# BMS029B_FETs.net
KiCad netlist of a schematic drawn in Altium Designer
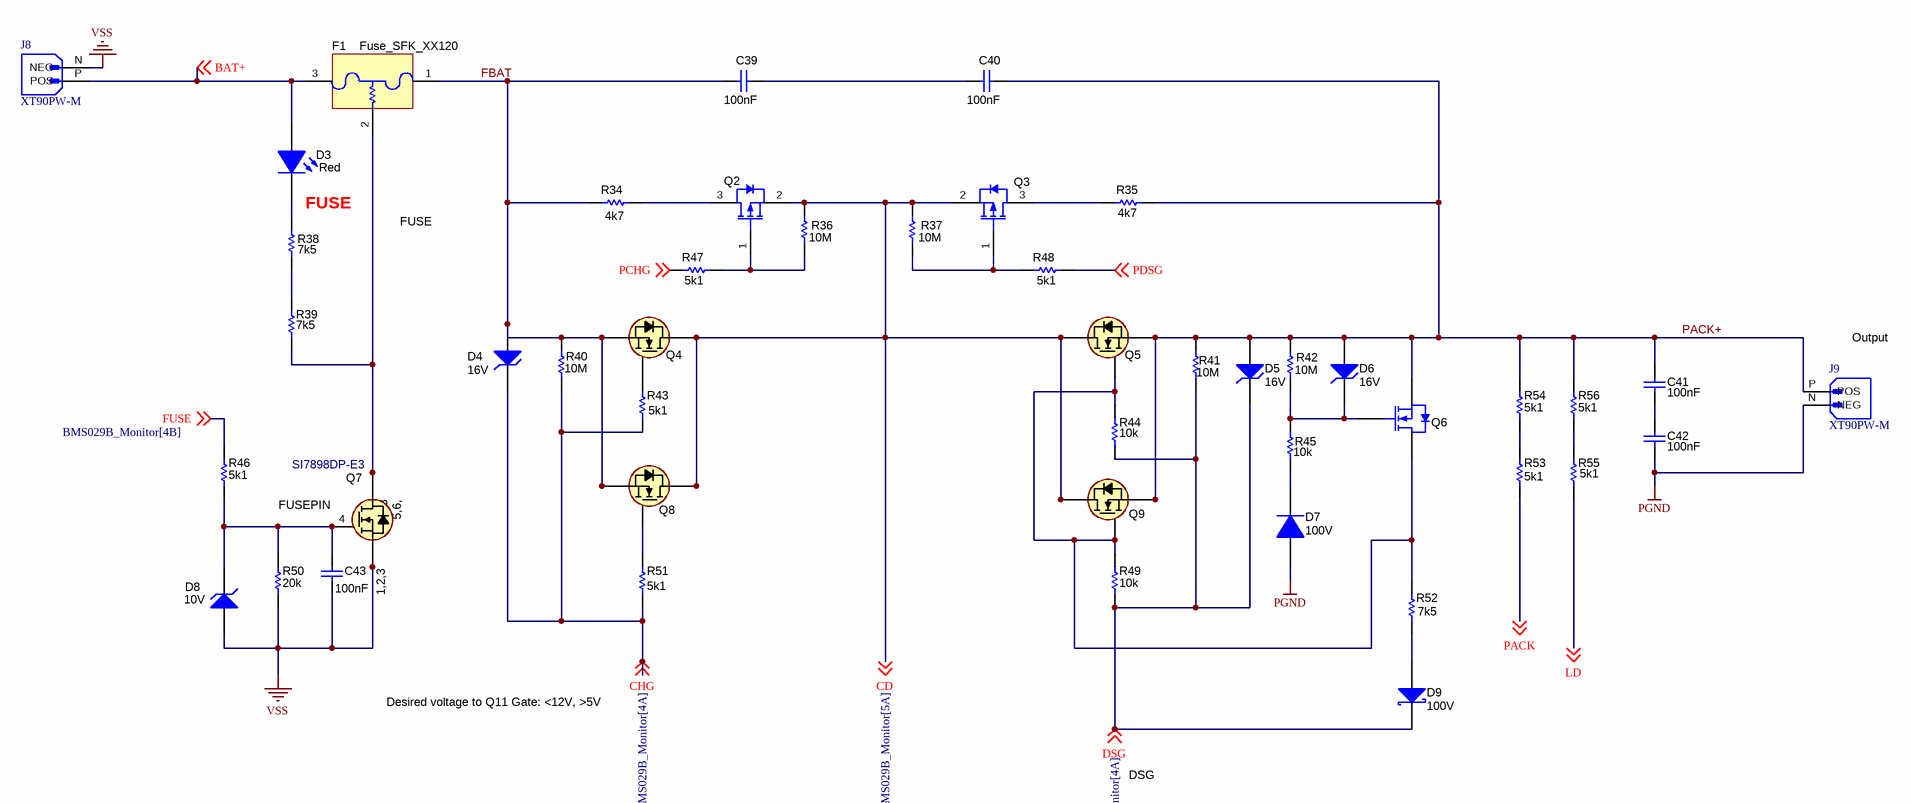
[diagram p0: BMS029B_FETs.SchDoc]

(export (version "E")
  (design (tool "Eeschema 10.0.6"))
  (components
    (comp (ref "C39")
      (value "100nF")
      (footprint "c0603")
      (description "CAP, CERM, 0.22 uF, 50 V, +/- 10%, X7R, 0603")
      (fields
        (field (name "MANUFACTURER") "TDK")
        (field (name "PARTNUMBER") "C1608X7R1H224K080AB")
        (field (name "PUBLISHER") "Texas Instruments")
      )
      (libsource (lib "worklib") (part "Capacitor"))
    )
    (comp (ref "C40")
      (value "100nF")
      (footprint "c0603")
      (description "CAP, CERM, 0.22 uF, 50 V, +/- 10%, X7R, 0603")
      (fields
        (field (name "MANUFACTURER") "TDK")
        (field (name "PARTNUMBER") "C1608X7R1H224K080AB")
        (field (name "PUBLISHER") "Texas Instruments")
      )
      (libsource (lib "worklib") (part "Capacitor"))
    )
    (comp (ref "C41")
      (value "100nF")
      (footprint "c0603")
      (description "CAP, CERM, 0.22 uF, 50 V, +/- 10%, X7R, 0603")
      (fields
        (field (name "MANUFACTURER") "TDK")
        (field (name "PARTNUMBER") "C1608X7R1H224K080AB")
        (field (name "PUBLISHER") "Texas Instruments")
      )
      (libsource (lib "worklib") (part "Capacitor"))
    )
    (comp (ref "C42")
      (value "100nF")
      (footprint "c0603")
      (description "CAP, CERM, 0.22 uF, 50 V, +/- 10%, X7R, 0603")
      (fields
        (field (name "MANUFACTURER") "TDK")
        (field (name "PARTNUMBER") "C1608X7R1H224K080AB")
        (field (name "PUBLISHER") "Texas Instruments")
      )
      (libsource (lib "worklib") (part "Capacitor"))
    )
    (comp (ref "C43")
      (value "100nF")
      (footprint "c0603")
      (description "CAP, CERM, 0.22 uF, 50 V, +/- 10%, X7R, 0603")
      (fields
        (field (name "PARTNUMBER") "C1608X7R1H224K080AB")
        (field (name "MANUFACTURER") "TDK")
        (field (name "PUBLISHER") "Texas Instruments")
      )
      (libsource (lib "worklib") (part "Capacitor"))
    )
    (comp (ref "D3")
      (value "Red")
      (footprint "WL-SMCW_RED")
      (description "LED, Red, SMD")
      (fields (field (name "MANUFACTURER") "Wurth Elektronik") (field (name "PARTNUMBER") "150060RS75000"))
      (libsource (lib "worklib") (part "CMP-0002947-3"))
    )
    (comp (ref "D4")
      (value "16V")
      (footprint "SOD-123")
      (description "Diode, Zener, 16 V, 500 mW, SOD-123")
      (fields (field (name "MANUFACTURER") "Diodes Inc.") (field (name "PARTNUMBER") "MMSZ5246B-7-F"))
      (libsource (lib "worklib") (part "Zener"))
    )
    (comp (ref "D5")
      (value "16V")
      (footprint "SOD-123")
      (description "Diode, Zener, 16 V, 500 mW, SOD-123")
      (fields (field (name "PARTNUMBER") "MMSZ5246B-7-F") (field (name "MANUFACTURER") "Diodes Inc."))
      (libsource (lib "worklib") (part "Zener"))
    )
    (comp (ref "D6")
      (value "16V")
      (footprint "SOD-123")
      (description "Diode, Zener, 16 V, 500 mW, SOD-123")
      (fields (field (name "PARTNUMBER") "MMSZ5246B-7-F") (field (name "MANUFACTURER") "Diodes Inc."))
      (libsource (lib "worklib") (part "Zener"))
    )
    (comp (ref "D7")
      (value "100V")
      (footprint "SOD-123")
      (description "Diode, Ultrafast, 100 V, 0.15 A, SOD-123")
      (fields (field (name "PARTNUMBER") "1N4148W-7-F") (field (name "MANUFACTURER") "Diodes Inc."))
      (libsource (lib "worklib") (part "CMP-0029001-2"))
    )
    (comp (ref "D8")
      (value "10V")
      (footprint "SOD-123")
      (description "Diode, Zener, 16 V, 500 mW, SOD-123")
      (fields (field (name "MANUFACTURER") "Diodes Inc.") (field (name "PARTNUMBER") "MMSZ5246B-7-F"))
      (libsource (lib "worklib") (part "Zener"))
    )
    (comp (ref "D9")
      (value "100V")
      (footprint "SOD-123")
      (description "Diode, Schottky, 100 V, 0.15 A, SOD-123")
      (fields (field (name "MANUFACTURER") "Diodes Inc.") (field (name "PARTNUMBER") "BAT46W-7-F"))
      (libsource (lib "worklib") (part "DIODE_SCHOTTKY"))
    )
    (comp (ref "F1")
      (value "Fuse_SFK_XX120")
      (footprint "120 Amperes SFM Series Self Control Protector(SCP)")
      (description "120 Amperes SFM Series Self Control Protector(SCP)")
      (fields (field (name "PARTNUMBER") "SFK-3030") (field (name "MANUFACTURER") "Dexerials Corporation"))
      (libsource (lib "worklib") (part "SFM-12120"))
    )
    (comp (ref "J8")
      (value "XT90PW-M")
      (footprint "AMASS_XT90PW-M")
      (description "Socket; DC supply; XT90; male; PIN: 2; on PCBs; THT; Colour: yellow")
      (fields (field (name "MF") "AMASS"))
      (libsource (lib "worklib") (part "XT90PW-M"))
    )
    (comp (ref "J9")
      (value "XT90PW-M")
      (footprint "AMASS_XT90PW-M")
      (description "Socket; DC supply; XT90; male; PIN: 2; on PCBs; THT; Colour: yellow")
      (fields (field (name "MF") "AMASS"))
      (libsource (lib "") (part "XT90PW-M_1"))
    )
    (comp (ref "Q2")
      (value "MOSFET_P_D3G1S2")
      (footprint "SOT-23")
      (description "MOSFET, P-CH, -150 V, -0.53 A, SOT-23")
      (libsource (lib "worklib") (part "MOSFET_P_D3G1S2"))
    )
    (comp (ref "Q3")
      (value "MOSFET_P_D3G1S2")
      (footprint "SOT-23")
      (description "MOSFET, P-CH, -150 V, -0.53 A, SOT-23")
      (libsource (lib "worklib") (part "MOSFET_P_D3G1S2"))
    )
    (comp (ref "Q4")
      (value "BSC160N15NS5ATMA1")
      (footprint "PG-TDSON-8")
      (description "MOSFET, N-CH, 150 V, 56 A, PG-TDSON-8")
      (fields
        (field (name "MANUFACTURER") "Infineon Technologies")
        (field (name "PUBLISHER") "Texas Instruments")
      )
      (libsource (lib "worklib") (part "MOSFET_N_D56789G"))
    )
    (comp (ref "Q5")
      (value "BSC160N15NS5ATMA1")
      (footprint "PG-TDSON-8")
      (description "MOSFET, N-CH, 150 V, 56 A, PG-TDSON-8")
      (fields
        (field (name "MANUFACTURER") "Infineon Technologies")
        (field (name "PUBLISHER") "Texas Instruments")
      )
      (libsource (lib "worklib") (part "MOSFET_N_D56789G"))
    )
    (comp (ref "Q6")
      (value "2N7002KW")
      (footprint "SOT-323")
      (description "MOSFET, N-CH, 60 V, 0.31 A, SOT-323")
      (fields
        (field (name "MANUFACTURER") "Fairchild Semiconductor")
        (field (name "PUBLISHER") "Texas Instruments")
      )
      (libsource (lib "worklib") (part "CMP-0000774-1"))
    )
    (comp (ref "Q7")
      (value "SI7898DP-E3")
      (footprint "PowerPAK_SO-8")
      (description "MOSFET, N-CH, 150 V, 13 A, PowerPACK SO-8")
      (fields
        (field (name "MANUFACTURER") "Infineon Technologies")
        (field (name "PARTNUMBER") "BSZ900N15NS3 G")
        (field (name "PUBLISHER") "Texas Instruments")
      )
      (libsource (lib "worklib") (part "SI7898DP-E3"))
    )
    (comp (ref "Q8")
      (value "BSC160N15NS5ATMA1")
      (footprint "PG-TDSON-8")
      (description "MOSFET, N-CH, 150 V, 56 A, PG-TDSON-8")
      (fields
        (field (name "MANUFACTURER") "Infineon Technologies")
        (field (name "PUBLISHER") "Texas Instruments")
      )
      (libsource (lib "worklib") (part "MOSFET_N_D56789G"))
    )
    (comp (ref "Q9")
      (value "BSC160N15NS5ATMA1")
      (footprint "PG-TDSON-8")
      (description "MOSFET, N-CH, 150 V, 56 A, PG-TDSON-8")
      (fields
        (field (name "MANUFACTURER") "Infineon Technologies")
        (field (name "PUBLISHER") "Texas Instruments")
      )
      (libsource (lib "worklib") (part "MOSFET_N_D56789G"))
    )
    (comp (ref "R34")
      (value "4k7")
      (footprint "2512")
      (description "RES, 20.0, 1%, 0.25 W, AEC-Q200 Grade 0, 1206")
      (fields (field (name "MANUFACTURER") "Vishay-Dale") (field (name "PARTNUMBER") "CRCW120620R0FKEA"))
      (libsource (lib "worklib") (part "Resistor_2512"))
    )
    (comp (ref "R35")
      (value "4k7")
      (footprint "2512")
      (description "RES, 20.0, 1%, 0.25 W, AEC-Q200 Grade 0, 1206")
      (fields (field (name "MANUFACTURER") "Vishay-Dale") (field (name "PARTNUMBER") "CRCW120620R0FKEA"))
      (libsource (lib "worklib") (part "Resistor_2512"))
    )
    (comp (ref "R36")
      (value "10M")
      (footprint "SMD 0805 res")
      (description "0.25 W, AEC-Q200 Grade 0, 0805")
      (fields (field (name "PARTNUMBER") "CRCW120620R0FKEA") (field (name "MANUFACTURER") "Vishay-Dale"))
      (libsource (lib "worklib") (part "Resistor_0805"))
    )
    (comp (ref "R37")
      (value "10M")
      (footprint "SMD 0805 res")
      (description "0.25 W, AEC-Q200 Grade 0, 0805")
      (fields (field (name "PARTNUMBER") "CRCW120620R0FKEA") (field (name "MANUFACTURER") "Vishay-Dale"))
      (libsource (lib "worklib") (part "Resistor_0805"))
    )
    (comp (ref "R38")
      (value "7k5")
      (footprint "SMD 0805 res")
      (description "0.25 W, AEC-Q200 Grade 0, 0805")
      (fields (field (name "MANUFACTURER") "Vishay-Dale") (field (name "PARTNUMBER") "CRCW120620R0FKEA"))
      (libsource (lib "worklib") (part "Resistor_0805"))
    )
    (comp (ref "R39")
      (value "7k5")
      (footprint "SMD 0805 res")
      (description "0.25 W, AEC-Q200 Grade 0, 0805")
      (fields (field (name "MANUFACTURER") "Vishay-Dale") (field (name "PARTNUMBER") "CRCW120620R0FKEA"))
      (libsource (lib "worklib") (part "Resistor_0805"))
    )
    (comp (ref "R40")
      (value "10M")
      (footprint "SMD 0805 res")
      (description "0.25 W, AEC-Q200 Grade 0, 0805")
      (fields (field (name "PARTNUMBER") "CRCW120620R0FKEA") (field (name "MANUFACTURER") "Vishay-Dale"))
      (libsource (lib "worklib") (part "Resistor_0805"))
    )
    (comp (ref "R41")
      (value "10M")
      (footprint "SMD 0805 res")
      (description "0.25 W, AEC-Q200 Grade 0, 0805")
      (fields (field (name "PARTNUMBER") "CRCW120620R0FKEA") (field (name "MANUFACTURER") "Vishay-Dale"))
      (libsource (lib "worklib") (part "Resistor_0805"))
    )
    (comp (ref "R42")
      (value "10M")
      (footprint "SMD 0805 res")
      (description "0.25 W, AEC-Q200 Grade 0, 0805")
      (fields (field (name "PARTNUMBER") "CRCW120620R0FKEA") (field (name "MANUFACTURER") "Vishay-Dale"))
      (libsource (lib "worklib") (part "Resistor_0805"))
    )
    (comp (ref "R43")
      (value "5k1")
      (footprint "SMD 0805 res")
      (description "0.25 W, AEC-Q200 Grade 0, 0805")
      (fields (field (name "PARTNUMBER") "CRCW120620R0FKEA") (field (name "MANUFACTURER") "Vishay-Dale"))
      (libsource (lib "worklib") (part "Resistor_0805"))
    )
    (comp (ref "R44")
      (value "10k")
      (footprint "SMD 0805 res")
      (description "0.25 W, AEC-Q200 Grade 0, 0805")
      (fields (field (name "PARTNUMBER") "CRCW120620R0FKEA") (field (name "MANUFACTURER") "Vishay-Dale"))
      (libsource (lib "worklib") (part "Resistor_0805"))
    )
    (comp (ref "R45")
      (value "10k")
      (footprint "SMD 0805 res")
      (description "0.25 W, AEC-Q200 Grade 0, 0805")
      (fields (field (name "PARTNUMBER") "CRCW120620R0FKEA") (field (name "MANUFACTURER") "Vishay-Dale"))
      (libsource (lib "worklib") (part "Resistor_0805"))
    )
    (comp (ref "R46")
      (value "5k1")
      (footprint "SMD 0805 res")
      (description "0.25 W, AEC-Q200 Grade 0, 0805")
      (fields (field (name "PARTNUMBER") "CRCW120620R0FKEA") (field (name "MANUFACTURER") "Vishay-Dale"))
      (libsource (lib "worklib") (part "Resistor_0805"))
    )
    (comp (ref "R47")
      (value "5k1")
      (footprint "SMD 0805 res")
      (description "0.25 W, AEC-Q200 Grade 0, 0805")
      (fields (field (name "PARTNUMBER") "CRCW120620R0FKEA") (field (name "MANUFACTURER") "Vishay-Dale"))
      (libsource (lib "worklib") (part "Resistor_0805"))
    )
    (comp (ref "R48")
      (value "5k1")
      (footprint "SMD 0805 res")
      (description "0.25 W, AEC-Q200 Grade 0, 0805")
      (fields (field (name "PARTNUMBER") "CRCW120620R0FKEA") (field (name "MANUFACTURER") "Vishay-Dale"))
      (libsource (lib "worklib") (part "Resistor_0805"))
    )
    (comp (ref "R49")
      (value "10k")
      (footprint "SMD 0805 res")
      (description "0.25 W, AEC-Q200 Grade 0, 0805")
      (fields (field (name "PARTNUMBER") "CRCW120620R0FKEA") (field (name "MANUFACTURER") "Vishay-Dale"))
      (libsource (lib "worklib") (part "Resistor_0805"))
    )
    (comp (ref "R50")
      (value "20k")
      (footprint "SMD 0805 res")
      (description "0.25 W, AEC-Q200 Grade 0, 0805")
      (fields (field (name "PARTNUMBER") "CRCW120620R0FKEA") (field (name "MANUFACTURER") "Vishay-Dale"))
      (libsource (lib "worklib") (part "Resistor_0805"))
    )
    (comp (ref "R51")
      (value "5k1")
      (footprint "SMD 0805 res")
      (description "0.25 W, AEC-Q200 Grade 0, 0805")
      (fields (field (name "PARTNUMBER") "CRCW120620R0FKEA") (field (name "MANUFACTURER") "Vishay-Dale"))
      (libsource (lib "worklib") (part "Resistor_0805"))
    )
    (comp (ref "R52")
      (value "7k5")
      (footprint "0603S")
      (description "RES, 100, 5%, 0.1 W, AEC-Q200 Grade 0, 0603")
      (fields
        (field (name "MANUFACTURER") "Vishay-Dale")
        (field (name "PARTNUMBER") "CRCW0603100RJNEA")
        (field (name "PUBLISHER") "Texas Instruments")
      )
      (libsource (lib "worklib") (part "Resistor_0603"))
    )
    (comp (ref "R53")
      (value "5k1")
      (footprint "SMD 0805 res")
      (description "0.25 W, AEC-Q200 Grade 0, 0805")
      (fields (field (name "PARTNUMBER") "CRCW120620R0FKEA") (field (name "MANUFACTURER") "Vishay-Dale"))
      (libsource (lib "worklib") (part "Resistor_0805"))
    )
    (comp (ref "R54")
      (value "5k1")
      (footprint "SMD 0805 res")
      (description "0.25 W, AEC-Q200 Grade 0, 0805")
      (fields (field (name "PARTNUMBER") "CRCW120620R0FKEA") (field (name "MANUFACTURER") "Vishay-Dale"))
      (libsource (lib "worklib") (part "Resistor_0805"))
    )
    (comp (ref "R55")
      (value "5k1")
      (footprint "SMD 0805 res")
      (description "0.25 W, AEC-Q200 Grade 0, 0805")
      (fields (field (name "PARTNUMBER") "CRCW120620R0FKEA") (field (name "MANUFACTURER") "Vishay-Dale"))
      (libsource (lib "worklib") (part "Resistor_0805"))
    )
    (comp (ref "R56")
      (value "5k1")
      (footprint "SMD 0805 res")
      (description "0.25 W, AEC-Q200 Grade 0, 0805")
      (fields (field (name "PARTNUMBER") "CRCW120620R0FKEA") (field (name "MANUFACTURER") "Vishay-Dale"))
      (libsource (lib "worklib") (part "Resistor_0805"))
    )
  )
  (nets
    (net (code "1") (name "/FBAT") (class "Default")
      (node (ref "C39") (pin "2") (pinfunction "2_2") (pintype "passive"))
      (node (ref "D4") (pin "2") (pinfunction "A_2") (pintype "passive"))
      (node (ref "F1") (pin "1") (pinfunction "Fuse_1") (pintype "passive"))
      (node (ref "Q4") (pin "1") (pinfunction "S_1") (pintype "passive"))
      (node (ref "Q4") (pin "2") (pinfunction "S_2") (pintype "passive"))
      (node (ref "Q4") (pin "3") (pinfunction "S_3") (pintype "passive"))
      (node (ref "Q8") (pin "1") (pinfunction "S_1") (pintype "passive"))
      (node (ref "Q8") (pin "2") (pinfunction "S_2") (pintype "passive"))
      (node (ref "Q8") (pin "3") (pinfunction "S_3") (pintype "passive"))
      (node (ref "R34") (pin "1") (pinfunction "1_1") (pintype "passive"))
      (node (ref "R40") (pin "2") (pinfunction "2_2") (pintype "passive"))
    )
    (net (code "2") (name "/PACK+") (class "Default")
      (node (ref "C40") (pin "1") (pinfunction "1_1") (pintype "passive"))
      (node (ref "C41") (pin "1") (pinfunction "1_1") (pintype "passive"))
      (node (ref "D5") (pin "2") (pinfunction "A_2") (pintype "passive"))
      (node (ref "D6") (pin "2") (pinfunction "A_2") (pintype "passive"))
      (node (ref "J9") (pin "P") (pinfunction "POS_P") (pintype "passive"))
      (node (ref "Q5") (pin "1") (pinfunction "S_1") (pintype "passive"))
      (node (ref "Q5") (pin "2") (pinfunction "S_2") (pintype "passive"))
      (node (ref "Q5") (pin "3") (pinfunction "S_3") (pintype "passive"))
      (node (ref "Q6") (pin "2") (pinfunction "S_2") (pintype "passive"))
      (node (ref "Q9") (pin "1") (pinfunction "S_1") (pintype "passive"))
      (node (ref "Q9") (pin "2") (pinfunction "S_2") (pintype "passive"))
      (node (ref "Q9") (pin "3") (pinfunction "S_3") (pintype "passive"))
      (node (ref "R35") (pin "2") (pinfunction "2_2") (pintype "passive"))
      (node (ref "R41") (pin "2") (pinfunction "2_2") (pintype "passive"))
      (node (ref "R42") (pin "2") (pinfunction "2_2") (pintype "passive"))
      (node (ref "R54") (pin "1") (pinfunction "1_1") (pintype "passive"))
      (node (ref "R56") (pin "1") (pinfunction "1_1") (pintype "passive"))
    )
    (net (code "3") (name "BAT+") (class "Default")
      (node (ref "D3") (pin "2") (pinfunction "A_2") (pintype "passive"))
      (node (ref "F1") (pin "3") (pinfunction "Fuse_3") (pintype "passive"))
      (node (ref "J8") (pin "P") (pinfunction "POS_P") (pintype "passive"))
    )
    (net (code "4") (name "CD") (class "Default")
      (node (ref "Q2") (pin "2") (pinfunction "S_2") (pintype "passive"))
      (node (ref "Q3") (pin "2") (pinfunction "S_2") (pintype "passive"))
      (node (ref "Q4") (pin "5") (pinfunction "D_5") (pintype "passive"))
      (node (ref "Q4") (pin "6") (pinfunction "D_6") (pintype "passive"))
      (node (ref "Q4") (pin "7") (pinfunction "D_7") (pintype "passive"))
      (node (ref "Q4") (pin "8") (pinfunction "D_8") (pintype "passive"))
      (node (ref "Q4") (pin "9") (pinfunction "D_9") (pintype "passive"))
      (node (ref "Q5") (pin "5") (pinfunction "D_5") (pintype "passive"))
      (node (ref "Q5") (pin "6") (pinfunction "D_6") (pintype "passive"))
      (node (ref "Q5") (pin "7") (pinfunction "D_7") (pintype "passive"))
      (node (ref "Q5") (pin "8") (pinfunction "D_8") (pintype "passive"))
      (node (ref "Q5") (pin "9") (pinfunction "D_9") (pintype "passive"))
      (node (ref "Q8") (pin "5") (pinfunction "D_5") (pintype "passive"))
      (node (ref "Q8") (pin "6") (pinfunction "D_6") (pintype "passive"))
      (node (ref "Q8") (pin "7") (pinfunction "D_7") (pintype "passive"))
      (node (ref "Q8") (pin "8") (pinfunction "D_8") (pintype "passive"))
      (node (ref "Q8") (pin "9") (pinfunction "D_9") (pintype "passive"))
      (node (ref "Q9") (pin "5") (pinfunction "D_5") (pintype "passive"))
      (node (ref "Q9") (pin "6") (pinfunction "D_6") (pintype "passive"))
      (node (ref "Q9") (pin "7") (pinfunction "D_7") (pintype "passive"))
      (node (ref "Q9") (pin "8") (pinfunction "D_8") (pintype "passive"))
      (node (ref "Q9") (pin "9") (pinfunction "D_9") (pintype "passive"))
      (node (ref "R36") (pin "2") (pinfunction "2_2") (pintype "passive"))
      (node (ref "R37") (pin "2") (pinfunction "2_2") (pintype "passive"))
    )
    (net (code "5") (name "CHG") (class "Default")
      (node (ref "D4") (pin "1") (pinfunction "K_1") (pintype "passive"))
      (node (ref "R40") (pin "1") (pinfunction "1_1") (pintype "passive"))
      (node (ref "R43") (pin "2") (pinfunction "2_2") (pintype "passive"))
      (node (ref "R51") (pin "2") (pinfunction "2_2") (pintype "passive"))
    )
    (net (code "6") (name "DSG") (class "Default")
      (node (ref "D5") (pin "1") (pinfunction "K_1") (pintype "passive"))
      (node (ref "D9") (pin "1") (pinfunction "K_1") (pintype "passive"))
      (node (ref "R41") (pin "1") (pinfunction "1_1") (pintype "passive"))
      (node (ref "R44") (pin "2") (pinfunction "2_2") (pintype "passive"))
      (node (ref "R49") (pin "2") (pinfunction "2_2") (pintype "passive"))
    )
    (net (code "7") (name "FUSE") (class "Default")
      (node (ref "R46") (pin "1") (pinfunction "1_1") (pintype "passive"))
    )
    (net (code "8") (name "LD") (class "Default")
      (node (ref "R55") (pin "2") (pinfunction "2_2") (pintype "passive"))
    )
    (net (code "9") (name "Net-(C39-Pad1)") (class "Default")
      (node (ref "C39") (pin "1") (pinfunction "1_1") (pintype "passive"))
      (node (ref "C40") (pin "2") (pinfunction "2_2") (pintype "passive"))
    )
    (net (code "10") (name "Net-(C41-Pad2)") (class "Default")
      (node (ref "C41") (pin "2") (pinfunction "2_2") (pintype "passive"))
      (node (ref "C42") (pin "1") (pinfunction "1_1") (pintype "passive"))
    )
    (net (code "11") (name "Net-(D3-K)") (class "Default")
      (node (ref "D3") (pin "1") (pinfunction "K_1") (pintype "passive"))
      (node (ref "R38") (pin "2") (pinfunction "2_2") (pintype "passive"))
    )
    (net (code "12") (name "Net-(D6-K)") (class "Default")
      (node (ref "D6") (pin "1") (pinfunction "K_1") (pintype "passive"))
      (node (ref "Q6") (pin "1") (pinfunction "G_1") (pintype "passive"))
      (node (ref "R42") (pin "1") (pinfunction "1_1") (pintype "passive"))
      (node (ref "R45") (pin "2") (pinfunction "2_2") (pintype "passive"))
    )
    (net (code "13") (name "Net-(D7-K)") (class "Default")
      (node (ref "D7") (pin "1") (pinfunction "K_1") (pintype "passive"))
      (node (ref "R45") (pin "1") (pinfunction "1_1") (pintype "passive"))
    )
    (net (code "14") (name "Net-(D8-K)") (class "Default")
      (node (ref "C43") (pin "2") (pinfunction "2_2") (pintype "passive"))
      (node (ref "D8") (pin "1") (pinfunction "K_1") (pintype "passive"))
      (node (ref "Q7") (pin "4") (pinfunction "G_4") (pintype "passive"))
      (node (ref "R46") (pin "2") (pinfunction "2_2") (pintype "passive"))
      (node (ref "R50") (pin "1") (pinfunction "1_1") (pintype "passive"))
    )
    (net (code "15") (name "Net-(D9-A)") (class "Default")
      (node (ref "D9") (pin "2") (pinfunction "A_2") (pintype "passive"))
      (node (ref "R52") (pin "2") (pinfunction "2_2") (pintype "passive"))
    )
    (net (code "16") (name "Net-(F1-Heater)") (class "Default")
      (node (ref "F1") (pin "2") (pinfunction "Heater_2") (pintype "passive"))
      (node (ref "Q7") (pin "5") (pinfunction "D_5") (pintype "passive"))
      (node (ref "Q7") (pin "6") (pinfunction "D_6") (pintype "passive"))
      (node (ref "Q7") (pin "7") (pinfunction "D_7") (pintype "passive"))
      (node (ref "Q7") (pin "8") (pinfunction "D_8") (pintype "passive"))
      (node (ref "Q7") (pin "9") (pinfunction "D_9") (pintype "passive"))
      (node (ref "R39") (pin "1") (pinfunction "1_1") (pintype "passive"))
    )
    (net (code "17") (name "Net-(Q2-D)") (class "Default")
      (node (ref "Q2") (pin "3") (pinfunction "D_3") (pintype "passive"))
      (node (ref "R34") (pin "2") (pinfunction "2_2") (pintype "passive"))
    )
    (net (code "18") (name "Net-(Q2-G)") (class "Default")
      (node (ref "Q2") (pin "1") (pinfunction "G_1") (pintype "passive"))
      (node (ref "R36") (pin "1") (pinfunction "1_1") (pintype "passive"))
      (node (ref "R47") (pin "2") (pinfunction "2_2") (pintype "passive"))
    )
    (net (code "19") (name "Net-(Q3-D)") (class "Default")
      (node (ref "Q3") (pin "3") (pinfunction "D_3") (pintype "passive"))
      (node (ref "R35") (pin "1") (pinfunction "1_1") (pintype "passive"))
    )
    (net (code "20") (name "Net-(Q3-G)") (class "Default")
      (node (ref "Q3") (pin "1") (pinfunction "G_1") (pintype "passive"))
      (node (ref "R37") (pin "1") (pinfunction "1_1") (pintype "passive"))
      (node (ref "R48") (pin "1") (pinfunction "1_1") (pintype "passive"))
    )
    (net (code "21") (name "Net-(Q4-G)") (class "Default")
      (node (ref "Q4") (pin "4") (pinfunction "G_4") (pintype "passive"))
      (node (ref "R43") (pin "1") (pinfunction "1_1") (pintype "passive"))
    )
    (net (code "22") (name "Net-(Q5-G)") (class "Default")
      (node (ref "Q5") (pin "4") (pinfunction "G_4") (pintype "passive"))
      (node (ref "Q6") (pin "3") (pinfunction "D_3") (pintype "passive"))
      (node (ref "Q9") (pin "4") (pinfunction "G_4") (pintype "passive"))
      (node (ref "R44") (pin "1") (pinfunction "1_1") (pintype "passive"))
      (node (ref "R49") (pin "1") (pinfunction "1_1") (pintype "passive"))
      (node (ref "R52") (pin "1") (pinfunction "1_1") (pintype "passive"))
    )
    (net (code "23") (name "Net-(Q8-G)") (class "Default")
      (node (ref "Q8") (pin "4") (pinfunction "G_4") (pintype "passive"))
      (node (ref "R51") (pin "1") (pinfunction "1_1") (pintype "passive"))
    )
    (net (code "24") (name "Net-(R38-Pad1)") (class "Default")
      (node (ref "R38") (pin "1") (pinfunction "1_1") (pintype "passive"))
      (node (ref "R39") (pin "2") (pinfunction "2_2") (pintype "passive"))
    )
    (net (code "25") (name "Net-(R53-Pad1)") (class "Default")
      (node (ref "R53") (pin "1") (pinfunction "1_1") (pintype "passive"))
      (node (ref "R54") (pin "2") (pinfunction "2_2") (pintype "passive"))
    )
    (net (code "26") (name "Net-(R55-Pad1)") (class "Default")
      (node (ref "R55") (pin "1") (pinfunction "1_1") (pintype "passive"))
      (node (ref "R56") (pin "2") (pinfunction "2_2") (pintype "passive"))
    )
    (net (code "27") (name "PACK") (class "Default")
      (node (ref "R53") (pin "2") (pinfunction "2_2") (pintype "passive"))
    )
    (net (code "28") (name "PCHG") (class "Default")
      (node (ref "R47") (pin "1") (pinfunction "1_1") (pintype "passive"))
    )
    (net (code "29") (name "PDSG") (class "Default")
      (node (ref "R48") (pin "2") (pinfunction "2_2") (pintype "passive"))
    )
    (net (code "30") (name "PGND") (class "Default")
      (node (ref "C42") (pin "2") (pinfunction "2_2") (pintype "passive"))
      (node (ref "D7") (pin "2") (pinfunction "A_2") (pintype "passive"))
      (node (ref "J9") (pin "N") (pinfunction "NEG_N") (pintype "passive"))
    )
    (net (code "31") (name "VSS") (class "Default")
      (node (ref "C43") (pin "1") (pinfunction "1_1") (pintype "passive"))
      (node (ref "D8") (pin "2") (pinfunction "A_2") (pintype "passive"))
      (node (ref "J8") (pin "N") (pinfunction "NEG_N") (pintype "passive"))
      (node (ref "Q7") (pin "1") (pinfunction "S_1") (pintype "passive"))
      (node (ref "Q7") (pin "2") (pinfunction "S_2") (pintype "passive"))
      (node (ref "Q7") (pin "3") (pinfunction "S_3") (pintype "passive"))
      (node (ref "R50") (pin "2") (pinfunction "2_2") (pintype "passive"))
    )
  )
)
